# PCB.net
KiCad netlist of a schematic drawn in EAGLE
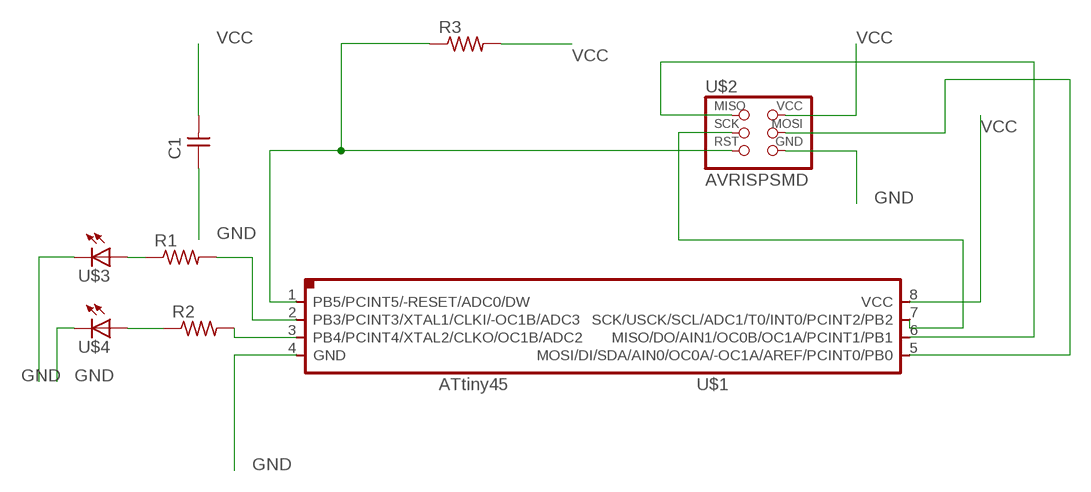
[diagram p0: schematic, sheet 1]

(export (version "E")
  (design (tool "Eeschema 10.0.6"))
  (components
    (comp (ref "C1")
      (value "UNPOLARIZED_CAPACITOR1206")
      (footprint "eagle-import:1206")
      (libsource (lib "eagle-import") (part "UNPOLARIZED_CAPACITOR1206"))
    )
    (comp (ref "R1")
      (value "RESISTOR1206")
      (footprint "eagle-import:1206")
      (libsource (lib "eagle-import") (part "RESISTOR1206"))
    )
    (comp (ref "R2")
      (value "RESISTOR1206")
      (footprint "eagle-import:1206")
      (libsource (lib "eagle-import") (part "RESISTOR1206"))
    )
    (comp (ref "R3")
      (value "RESISTOR1206")
      (footprint "eagle-import:1206")
      (libsource (lib "eagle-import") (part "RESISTOR1206"))
    )
    (comp (ref "U$1")
      (value "ATTINY45SI")
      (footprint "eagle-import:SOIC8")
      (libsource (lib "eagle-import") (part "ATTINY45SI"))
    )
    (comp (ref "U$2")
      (value "AVRISPSMD")
      (footprint "eagle-import:2X03SMD")
      (libsource (lib "eagle-import") (part "AVRISPSMD"))
    )
    (comp (ref "U$3")
      (value "LED1206")
      (footprint "eagle-import:1206")
      (libsource (lib "eagle-import") (part "LED1206"))
    )
    (comp (ref "U$4")
      (value "LED1206")
      (footprint "eagle-import:1206")
      (libsource (lib "eagle-import") (part "LED1206"))
    )
  )
  (nets
    (net (code "1") (name "/GND") (class "Default")
      (node (ref "C1") (pin "1") (pinfunction "1_1") (pintype "passive"))
      (node (ref "U$1") (pin "4") (pinfunction "GND_4") (pintype "bidirectional"))
      (node (ref "U$2") (pin "6") (pinfunction "GND_6") (pintype "passive"))
      (node (ref "U$3") (pin "2") (pinfunction "C_2") (pintype "passive"))
      (node (ref "U$4") (pin "2") (pinfunction "C_2") (pintype "passive"))
    )
    (net (code "2") (name "/VCC") (class "Default")
      (node (ref "C1") (pin "2") (pinfunction "2_2") (pintype "passive"))
      (node (ref "R3") (pin "2") (pinfunction "2_2") (pintype "passive"))
      (node (ref "U$1") (pin "8") (pinfunction "VCC_8") (pintype "bidirectional"))
      (node (ref "U$2") (pin "2") (pinfunction "VCC_2") (pintype "passive"))
    )
    (net (code "3") (name "Net-(U$1-MISO{slash}DO{slash}AIN1{slash}OC0B{slash}OC1A{slash}PCINT1{slash}PB1)") (class "Default")
      (node (ref "U$1") (pin "6") (pinfunction "MISO/DO/AIN1/OC0B/OC1A/PCINT1/PB1_6") (pintype "bidirectional"))
      (node (ref "U$2") (pin "1") (pinfunction "MISO_1") (pintype "passive"))
    )
    (net (code "4") (name "Net-(U$1-MOSI{slash}DI{slash}SDA{slash}AIN0{slash}OC0A{slash}-OC1A{slash}AREF{slash}PCINT0{slash}PB0)") (class "Default")
      (node (ref "U$1") (pin "5") (pinfunction "MOSI/DI/SDA/AIN0/OC0A/-OC1A/AREF/PCINT0/PB0_5") (pintype "bidirectional"))
      (node (ref "U$2") (pin "4") (pinfunction "MOSI_4") (pintype "passive"))
    )
    (net (code "5") (name "Net-(U$1-PB3{slash}PCINT3{slash}XTAL1{slash}CLKI{slash}-OC1B{slash}ADC3)") (class "Default")
      (node (ref "R1") (pin "2") (pinfunction "2_2") (pintype "passive"))
      (node (ref "U$1") (pin "2") (pinfunction "PB3/PCINT3/XTAL1/CLKI/-OC1B/ADC3_2") (pintype "bidirectional"))
    )
    (net (code "6") (name "Net-(U$1-PB4{slash}PCINT4{slash}XTAL2{slash}CLKO{slash}OC1B{slash}ADC2)") (class "Default")
      (node (ref "R2") (pin "2") (pinfunction "2_2") (pintype "passive"))
      (node (ref "U$1") (pin "3") (pinfunction "PB4/PCINT4/XTAL2/CLKO/OC1B/ADC2_3") (pintype "bidirectional"))
    )
    (net (code "7") (name "Net-(U$1-PB5{slash}PCINT5{slash}-RESET{slash}ADC0{slash}DW)") (class "Default")
      (node (ref "R3") (pin "1") (pinfunction "1_1") (pintype "passive"))
      (node (ref "U$1") (pin "1") (pinfunction "PB5/PCINT5/-RESET/ADC0/DW_1") (pintype "bidirectional"))
      (node (ref "U$2") (pin "5") (pinfunction "RST_5") (pintype "passive"))
    )
    (net (code "8") (name "Net-(U$1-SCK{slash}USCK{slash}SCL{slash}ADC1{slash}T0{slash}INT0{slash}PCINT2{slash}PB2)") (class "Default")
      (node (ref "U$1") (pin "7") (pinfunction "SCK/USCK/SCL/ADC1/T0/INT0/PCINT2/PB2_7") (pintype "bidirectional"))
      (node (ref "U$2") (pin "3") (pinfunction "SCK_3") (pintype "passive"))
    )
    (net (code "9") (name "Net-(U$3-A)") (class "Default")
      (node (ref "R1") (pin "1") (pinfunction "1_1") (pintype "passive"))
      (node (ref "U$3") (pin "1") (pinfunction "A_1") (pintype "passive"))
    )
    (net (code "10") (name "Net-(U$4-A)") (class "Default")
      (node (ref "R2") (pin "1") (pinfunction "1_1") (pintype "passive"))
      (node (ref "U$4") (pin "1") (pinfunction "A_1") (pintype "passive"))
    )
  )
)
